# Display_Hour.net
KiCad netlist of a schematic drawn in Altium Designer
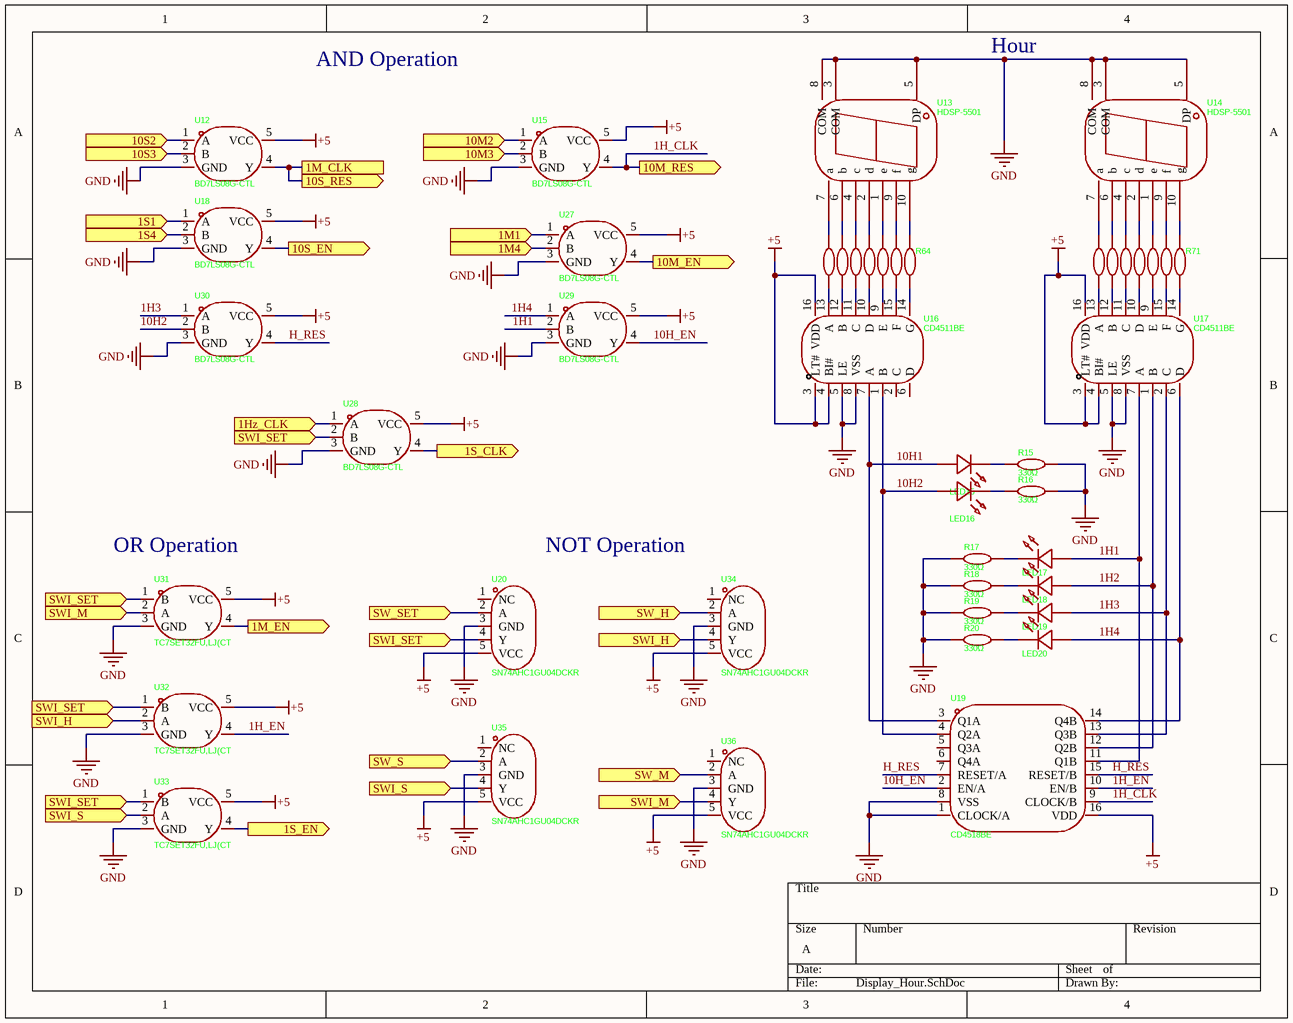
[diagram p0: Display_Hour.SchDoc]

(export (version "E")
  (design (tool "Eeschema 10.0.6"))
  (components
    (comp (ref "LED15")
      (value "WP7113ID")
      (footprint "LED-TH_BD5.0-P2.54-FD")
      (fields (field (name "MANUFACTURER") "Kingbright"))
      (libsource (lib "BCD_Clock_SCH_lib") (part "D_LED_2mm_red"))
    )
    (comp (ref "LED16")
      (value "WP7113ID")
      (footprint "LED-TH_BD5.0-P2.54-FD")
      (fields (field (name "MANUFACTURER") "Kingbright"))
      (libsource (lib "BCD_Clock_SCH_lib") (part "D_LED_2mm_red"))
    )
    (comp (ref "LED17")
      (value "WP7113ID")
      (footprint "LED-TH_BD5.0-P2.54-FD")
      (fields (field (name "MANUFACTURER") "Kingbright"))
      (libsource (lib "BCD_Clock_SCH_lib") (part "D_LED_2mm_red"))
    )
    (comp (ref "LED18")
      (value "WP7113ID")
      (footprint "LED-TH_BD5.0-P2.54-FD")
      (fields (field (name "MANUFACTURER") "Kingbright"))
      (libsource (lib "BCD_Clock_SCH_lib") (part "D_LED_2mm_red"))
    )
    (comp (ref "LED19")
      (value "WP7113ID")
      (footprint "LED-TH_BD5.0-P2.54-FD")
      (fields (field (name "MANUFACTURER") "Kingbright"))
      (libsource (lib "BCD_Clock_SCH_lib") (part "D_LED_2mm_red"))
    )
    (comp (ref "LED20")
      (value "WP7113ID")
      (footprint "LED-TH_BD5.0-P2.54-FD")
      (fields (field (name "MANUFACTURER") "Kingbright"))
      (libsource (lib "BCD_Clock_SCH_lib") (part "D_LED_2mm_red"))
    )
    (comp (ref "R15")
      (value "330Ω")
      (footprint "RES-TH_BD2.3-L6.5-P10.50-D0.5")
      (fields
        (field (name "MANUFACTURER") "CCO(千志电子)")
        (field (name "MANUFACTURER PART") "MF1/4W-330Ω±1% T")
        (field (name "TOLERANCE") "±1%")
      )
      (libsource (lib "BCD_Clock_SCH_lib") (part "Reg_330R_0.25W"))
    )
    (comp (ref "R16")
      (value "330Ω")
      (footprint "RES-TH_BD2.3-L6.5-P10.50-D0.5")
      (fields
        (field (name "MANUFACTURER") "CCO(千志电子)")
        (field (name "MANUFACTURER PART") "MF1/4W-330Ω±1% T")
        (field (name "TOLERANCE") "±1%")
      )
      (libsource (lib "BCD_Clock_SCH_lib") (part "Reg_330R_0.25W"))
    )
    (comp (ref "R17")
      (value "330Ω")
      (footprint "RES-TH_BD2.3-L6.5-P10.50-D0.5")
      (fields
        (field (name "MANUFACTURER") "CCO(千志电子)")
        (field (name "MANUFACTURER PART") "MF1/4W-330Ω±1% T")
        (field (name "TOLERANCE") "±1%")
      )
      (libsource (lib "BCD_Clock_SCH_lib") (part "Reg_330R_0.25W"))
    )
    (comp (ref "R18")
      (value "330Ω")
      (footprint "RES-TH_BD2.3-L6.5-P10.50-D0.5")
      (fields
        (field (name "MANUFACTURER") "CCO(千志电子)")
        (field (name "MANUFACTURER PART") "MF1/4W-330Ω±1% T")
        (field (name "TOLERANCE") "±1%")
      )
      (libsource (lib "BCD_Clock_SCH_lib") (part "Reg_330R_0.25W"))
    )
    (comp (ref "R19")
      (value "330Ω")
      (footprint "RES-TH_BD2.3-L6.5-P10.50-D0.5")
      (fields
        (field (name "MANUFACTURER") "CCO(千志电子)")
        (field (name "MANUFACTURER PART") "MF1/4W-330Ω±1% T")
        (field (name "TOLERANCE") "±1%")
      )
      (libsource (lib "BCD_Clock_SCH_lib") (part "Reg_330R_0.25W"))
    )
    (comp (ref "R20")
      (value "330Ω")
      (footprint "RES-TH_BD2.3-L6.5-P10.50-D0.5")
      (fields
        (field (name "MANUFACTURER") "CCO(千志电子)")
        (field (name "MANUFACTURER PART") "MF1/4W-330Ω±1% T")
        (field (name "TOLERANCE") "±1%")
      )
      (libsource (lib "BCD_Clock_SCH_lib") (part "Reg_330R_0.25W"))
    )
    (comp (ref "R58")
      (value "330Ω")
      (footprint "RES-TH_BD2.3-L6.5-P10.50-D0.5")
      (fields
        (field (name "MANUFACTURER") "CCO(千志电子)")
        (field (name "MANUFACTURER PART") "MF1/4W-330Ω±1% T")
        (field (name "TOLERANCE") "±1%")
      )
      (libsource (lib "BCD_Clock_SCH_lib") (part "Reg_330R_0.25W"))
    )
    (comp (ref "R59")
      (value "330Ω")
      (footprint "RES-TH_BD2.3-L6.5-P10.50-D0.5")
      (fields
        (field (name "MANUFACTURER") "CCO(千志电子)")
        (field (name "MANUFACTURER PART") "MF1/4W-330Ω±1% T")
        (field (name "TOLERANCE") "±1%")
      )
      (libsource (lib "BCD_Clock_SCH_lib") (part "Reg_330R_0.25W"))
    )
    (comp (ref "R60")
      (value "330Ω")
      (footprint "RES-TH_BD2.3-L6.5-P10.50-D0.5")
      (fields
        (field (name "MANUFACTURER") "CCO(千志电子)")
        (field (name "MANUFACTURER PART") "MF1/4W-330Ω±1% T")
        (field (name "TOLERANCE") "±1%")
      )
      (libsource (lib "BCD_Clock_SCH_lib") (part "Reg_330R_0.25W"))
    )
    (comp (ref "R61")
      (value "330Ω")
      (footprint "RES-TH_BD2.3-L6.5-P10.50-D0.5")
      (fields
        (field (name "MANUFACTURER") "CCO(千志电子)")
        (field (name "MANUFACTURER PART") "MF1/4W-330Ω±1% T")
        (field (name "TOLERANCE") "±1%")
      )
      (libsource (lib "BCD_Clock_SCH_lib") (part "Reg_330R_0.25W"))
    )
    (comp (ref "R62")
      (value "330Ω")
      (footprint "RES-TH_BD2.3-L6.5-P10.50-D0.5")
      (fields
        (field (name "MANUFACTURER") "CCO(千志电子)")
        (field (name "MANUFACTURER PART") "MF1/4W-330Ω±1% T")
        (field (name "TOLERANCE") "±1%")
      )
      (libsource (lib "BCD_Clock_SCH_lib") (part "Reg_330R_0.25W"))
    )
    (comp (ref "R63")
      (value "330Ω")
      (footprint "RES-TH_BD2.3-L6.5-P10.50-D0.5")
      (fields
        (field (name "MANUFACTURER") "CCO(千志电子)")
        (field (name "MANUFACTURER PART") "MF1/4W-330Ω±1% T")
        (field (name "TOLERANCE") "±1%")
      )
      (libsource (lib "BCD_Clock_SCH_lib") (part "Reg_330R_0.25W"))
    )
    (comp (ref "R64")
      (value "330Ω")
      (footprint "RES-TH_BD2.3-L6.5-P10.50-D0.5")
      (fields
        (field (name "MANUFACTURER") "CCO(千志电子)")
        (field (name "MANUFACTURER PART") "MF1/4W-330Ω±1% T")
        (field (name "TOLERANCE") "±1%")
      )
      (libsource (lib "BCD_Clock_SCH_lib") (part "Reg_330R_0.25W"))
    )
    (comp (ref "R65")
      (value "330Ω")
      (footprint "RES-TH_BD2.3-L6.5-P10.50-D0.5")
      (fields
        (field (name "MANUFACTURER") "CCO(千志电子)")
        (field (name "MANUFACTURER PART") "MF1/4W-330Ω±1% T")
        (field (name "TOLERANCE") "±1%")
      )
      (libsource (lib "BCD_Clock_SCH_lib") (part "Reg_330R_0.25W"))
    )
    (comp (ref "R66")
      (value "330Ω")
      (footprint "RES-TH_BD2.3-L6.5-P10.50-D0.5")
      (fields
        (field (name "MANUFACTURER") "CCO(千志电子)")
        (field (name "MANUFACTURER PART") "MF1/4W-330Ω±1% T")
        (field (name "TOLERANCE") "±1%")
      )
      (libsource (lib "BCD_Clock_SCH_lib") (part "Reg_330R_0.25W"))
    )
    (comp (ref "R67")
      (value "330Ω")
      (footprint "RES-TH_BD2.3-L6.5-P10.50-D0.5")
      (fields
        (field (name "MANUFACTURER") "CCO(千志电子)")
        (field (name "MANUFACTURER PART") "MF1/4W-330Ω±1% T")
        (field (name "TOLERANCE") "±1%")
      )
      (libsource (lib "BCD_Clock_SCH_lib") (part "Reg_330R_0.25W"))
    )
    (comp (ref "R68")
      (value "330Ω")
      (footprint "RES-TH_BD2.3-L6.5-P10.50-D0.5")
      (fields
        (field (name "MANUFACTURER") "CCO(千志电子)")
        (field (name "MANUFACTURER PART") "MF1/4W-330Ω±1% T")
        (field (name "TOLERANCE") "±1%")
      )
      (libsource (lib "BCD_Clock_SCH_lib") (part "Reg_330R_0.25W"))
    )
    (comp (ref "R69")
      (value "330Ω")
      (footprint "RES-TH_BD2.3-L6.5-P10.50-D0.5")
      (fields
        (field (name "MANUFACTURER") "CCO(千志电子)")
        (field (name "MANUFACTURER PART") "MF1/4W-330Ω±1% T")
        (field (name "TOLERANCE") "±1%")
      )
      (libsource (lib "BCD_Clock_SCH_lib") (part "Reg_330R_0.25W"))
    )
    (comp (ref "R70")
      (value "330Ω")
      (footprint "RES-TH_BD2.3-L6.5-P10.50-D0.5")
      (fields
        (field (name "MANUFACTURER") "CCO(千志电子)")
        (field (name "MANUFACTURER PART") "MF1/4W-330Ω±1% T")
        (field (name "TOLERANCE") "±1%")
      )
      (libsource (lib "BCD_Clock_SCH_lib") (part "Reg_330R_0.25W"))
    )
    (comp (ref "R71")
      (value "330Ω")
      (footprint "RES-TH_BD2.3-L6.5-P10.50-D0.5")
      (fields
        (field (name "MANUFACTURER") "CCO(千志电子)")
        (field (name "MANUFACTURER PART") "MF1/4W-330Ω±1% T")
        (field (name "TOLERANCE") "±1%")
      )
      (libsource (lib "BCD_Clock_SCH_lib") (part "Reg_330R_0.25W"))
    )
    (comp (ref "U12")
      (value "BD7LS08G-CTL")
      (footprint "SSOP-5_L3.0-W1.6-P0.95-LS2.8-BR")
      (fields (field (name "MANUFACTURER") "ROHM(罗姆)"))
      (libsource (lib "BCD_Clock_SCH_lib") (part "AND_BD7LS08G-CTL"))
    )
    (comp (ref "U13")
      (value "HDSP-5501")
      (footprint "LED-SEG-TH_HDSP-A")
      (fields (field (name "MANUFACTURER") "Broadcom/AVAGO(安华高)"))
      (libsource (lib "BCD_Clock_SCH_lib") (part "HDSP-5501"))
    )
    (comp (ref "U14")
      (value "HDSP-5501")
      (footprint "LED-SEG-TH_HDSP-A")
      (fields (field (name "MANUFACTURER") "Broadcom/AVAGO(安华高)"))
      (libsource (lib "BCD_Clock_SCH_lib") (part "HDSP-5501"))
    )
    (comp (ref "U15")
      (value "BD7LS08G-CTL")
      (footprint "SSOP-5_L3.0-W1.6-P0.95-LS2.8-BR")
      (fields (field (name "MANUFACTURER") "ROHM(罗姆)"))
      (libsource (lib "BCD_Clock_SCH_lib") (part "AND_BD7LS08G-CTL"))
    )
    (comp (ref "U16")
      (value "CD4511BE")
      (footprint "DIP-16_L19.8-W6.5-P2.54-LS7.6-BL")
      (fields (field (name "MANUFACTURER") "HGSEMI(华冠)"))
      (libsource (lib "BCD_Clock_SCH_lib") (part "CD4511BE_C507153"))
    )
    (comp (ref "U17")
      (value "CD4511BE")
      (footprint "DIP-16_L19.8-W6.5-P2.54-LS7.6-BL")
      (fields (field (name "MANUFACTURER") "HGSEMI(华冠)"))
      (libsource (lib "BCD_Clock_SCH_lib") (part "CD4511BE_C507153"))
    )
    (comp (ref "U18")
      (value "BD7LS08G-CTL")
      (footprint "SSOP-5_L3.0-W1.6-P0.95-LS2.8-BR")
      (fields (field (name "MANUFACTURER") "ROHM(罗姆)"))
      (libsource (lib "BCD_Clock_SCH_lib") (part "AND_BD7LS08G-CTL"))
    )
    (comp (ref "U19")
      (value "CD4518BE")
      (footprint "DIP-16_L19.3-W6.4-P2.54-LS7.6-BL")
      (fields (field (name "MANUFACTURER") "TI(德州仪器)"))
      (libsource (lib "BCD_Clock_SCH_lib") (part "CD4518BE"))
    )
    (comp (ref "U20")
      (value "SN74AHC1GU04DCKR")
      (footprint "SOT-353_L2.1-W1.3-P0.65-LS2.3-BR")
      (fields (field (name "MANUFACTURER") "TI(德州仪器)"))
      (libsource (lib "BCD_Clock_SCH_lib") (part "NOT_SN74AHC1GU04DCKR_C7472"))
    )
    (comp (ref "U27")
      (value "BD7LS08G-CTL")
      (footprint "SSOP-5_L3.0-W1.6-P0.95-LS2.8-BR")
      (fields (field (name "MANUFACTURER") "ROHM(罗姆)"))
      (libsource (lib "BCD_Clock_SCH_lib") (part "AND_BD7LS08G-CTL"))
    )
    (comp (ref "U28")
      (value "BD7LS08G-CTL")
      (footprint "SSOP-5_L3.0-W1.6-P0.95-LS2.8-BR")
      (fields (field (name "MANUFACTURER") "ROHM(罗姆)"))
      (libsource (lib "BCD_Clock_SCH_lib") (part "AND_BD7LS08G-CTL"))
    )
    (comp (ref "U29")
      (value "BD7LS08G-CTL")
      (footprint "SSOP-5_L3.0-W1.6-P0.95-LS2.8-BR")
      (fields (field (name "MANUFACTURER") "ROHM(罗姆)"))
      (libsource (lib "BCD_Clock_SCH_lib") (part "AND_BD7LS08G-CTL"))
    )
    (comp (ref "U30")
      (value "BD7LS08G-CTL")
      (footprint "SSOP-5_L3.0-W1.6-P0.95-LS2.8-BR")
      (fields (field (name "MANUFACTURER") "ROHM(罗姆)"))
      (libsource (lib "BCD_Clock_SCH_lib") (part "AND_BD7LS08G-CTL"))
    )
    (comp (ref "U31")
      (value "TC7SET32FU,LJ(CT")
      (footprint "TSSOP-5_L2.0-W1.3-P0.65-LS2.1-BR")
      (fields (field (name "MANUFACTURER") "TOSHIBA(东芝)"))
      (libsource (lib "BCD_Clock_SCH_lib") (part "OR_GATE_TC7SET32FU,LJ(CT"))
    )
    (comp (ref "U32")
      (value "TC7SET32FU,LJ(CT")
      (footprint "TSSOP-5_L2.0-W1.3-P0.65-LS2.1-BR")
      (fields (field (name "MANUFACTURER") "TOSHIBA(东芝)"))
      (libsource (lib "BCD_Clock_SCH_lib") (part "OR_GATE_TC7SET32FU,LJ(CT"))
    )
    (comp (ref "U33")
      (value "TC7SET32FU,LJ(CT")
      (footprint "TSSOP-5_L2.0-W1.3-P0.65-LS2.1-BR")
      (fields (field (name "MANUFACTURER") "TOSHIBA(东芝)"))
      (libsource (lib "BCD_Clock_SCH_lib") (part "OR_GATE_TC7SET32FU,LJ(CT"))
    )
    (comp (ref "U34")
      (value "SN74AHC1GU04DCKR")
      (footprint "SOT-353_L2.1-W1.3-P0.65-LS2.3-BR")
      (fields (field (name "MANUFACTURER") "TI(德州仪器)"))
      (libsource (lib "BCD_Clock_SCH_lib") (part "NOT_SN74AHC1GU04DCKR_C7472"))
    )
    (comp (ref "U35")
      (value "SN74AHC1GU04DCKR")
      (footprint "SOT-353_L2.1-W1.3-P0.65-LS2.3-BR")
      (fields (field (name "MANUFACTURER") "TI(德州仪器)"))
      (libsource (lib "BCD_Clock_SCH_lib") (part "NOT_SN74AHC1GU04DCKR_C7472"))
    )
    (comp (ref "U36")
      (value "SN74AHC1GU04DCKR")
      (footprint "SOT-353_L2.1-W1.3-P0.65-LS2.3-BR")
      (fields (field (name "MANUFACTURER") "TI(德州仪器)"))
      (libsource (lib "BCD_Clock_SCH_lib") (part "NOT_SN74AHC1GU04DCKR_C7472"))
    )
  )
  (nets
    (net (code "1") (name "+5") (class "Default")
      (node (ref "U12") (pin "5") (pinfunction "VCC_5") (pintype "passive"))
      (node (ref "U15") (pin "5") (pinfunction "VCC_5") (pintype "passive"))
      (node (ref "U16") (pin "16") (pinfunction "VDD_16") (pintype "passive"))
      (node (ref "U16") (pin "3") (pinfunction "LT#_3") (pintype "passive"))
      (node (ref "U16") (pin "4") (pinfunction "BI#_4") (pintype "passive"))
      (node (ref "U17") (pin "16") (pinfunction "VDD_16") (pintype "passive"))
      (node (ref "U17") (pin "3") (pinfunction "LT#_3") (pintype "passive"))
      (node (ref "U17") (pin "4") (pinfunction "BI#_4") (pintype "passive"))
      (node (ref "U18") (pin "5") (pinfunction "VCC_5") (pintype "passive"))
      (node (ref "U19") (pin "16") (pinfunction "VDD_16") (pintype "passive"))
      (node (ref "U20") (pin "5") (pinfunction "VCC_5") (pintype "passive"))
      (node (ref "U27") (pin "5") (pinfunction "VCC_5") (pintype "passive"))
      (node (ref "U28") (pin "5") (pinfunction "VCC_5") (pintype "passive"))
      (node (ref "U29") (pin "5") (pinfunction "VCC_5") (pintype "passive"))
      (node (ref "U30") (pin "5") (pinfunction "VCC_5") (pintype "passive"))
      (node (ref "U31") (pin "5") (pinfunction "VCC_5") (pintype "passive"))
      (node (ref "U32") (pin "5") (pinfunction "VCC_5") (pintype "passive"))
      (node (ref "U33") (pin "5") (pinfunction "VCC_5") (pintype "passive"))
      (node (ref "U34") (pin "5") (pinfunction "VCC_5") (pintype "passive"))
      (node (ref "U35") (pin "5") (pinfunction "VCC_5") (pintype "passive"))
      (node (ref "U36") (pin "5") (pinfunction "VCC_5") (pintype "passive"))
    )
    (net (code "2") (name "/1H1") (class "Default")
      (node (ref "LED17") (pin "1") (pinfunction "A_1") (pintype "passive"))
      (node (ref "U17") (pin "7") (pinfunction "A_7") (pintype "passive"))
      (node (ref "U19") (pin "11") (pinfunction "Q1B_11") (pintype "passive"))
      (node (ref "U29") (pin "2") (pinfunction "B_2") (pintype "passive"))
    )
    (net (code "3") (name "/1H2") (class "Default")
      (node (ref "LED18") (pin "1") (pinfunction "A_1") (pintype "passive"))
      (node (ref "U17") (pin "1") (pinfunction "B_1") (pintype "passive"))
      (node (ref "U19") (pin "12") (pinfunction "Q2B_12") (pintype "passive"))
    )
    (net (code "4") (name "/1H3") (class "Default")
      (node (ref "LED19") (pin "1") (pinfunction "A_1") (pintype "passive"))
      (node (ref "U17") (pin "2") (pinfunction "C_2") (pintype "passive"))
      (node (ref "U19") (pin "13") (pinfunction "Q3B_13") (pintype "passive"))
      (node (ref "U30") (pin "1") (pinfunction "A_1") (pintype "passive"))
    )
    (net (code "5") (name "/1H4") (class "Default")
      (node (ref "LED20") (pin "1") (pinfunction "A_1") (pintype "passive"))
      (node (ref "U17") (pin "6") (pinfunction "D_6") (pintype "passive"))
      (node (ref "U19") (pin "14") (pinfunction "Q4B_14") (pintype "passive"))
      (node (ref "U29") (pin "1") (pinfunction "A_1") (pintype "passive"))
    )
    (net (code "6") (name "/1H_CLK") (class "Default")
      (node (ref "U15") (pin "4") (pinfunction "Y_4") (pintype "passive"))
      (node (ref "U19") (pin "9") (pinfunction "CLOCK/B_9") (pintype "passive"))
    )
    (net (code "7") (name "/1H_EN") (class "Default")
      (node (ref "U19") (pin "10") (pinfunction "EN/B_10") (pintype "passive"))
      (node (ref "U32") (pin "4") (pinfunction "Y_4") (pintype "passive"))
    )
    (net (code "8") (name "/1Hz_CLK") (class "Default")
      (node (ref "U28") (pin "1") (pinfunction "A_1") (pintype "passive"))
    )
    (net (code "9") (name "/1M1") (class "Default")
      (node (ref "U27") (pin "1") (pinfunction "A_1") (pintype "passive"))
    )
    (net (code "10") (name "/1M4") (class "Default")
      (node (ref "U27") (pin "2") (pinfunction "B_2") (pintype "passive"))
    )
    (net (code "11") (name "/1M_EN") (class "Default")
      (node (ref "U31") (pin "4") (pinfunction "Y_4") (pintype "passive"))
    )
    (net (code "12") (name "/1S1") (class "Default")
      (node (ref "U18") (pin "1") (pinfunction "A_1") (pintype "passive"))
    )
    (net (code "13") (name "/1S4") (class "Default")
      (node (ref "U18") (pin "2") (pinfunction "B_2") (pintype "passive"))
    )
    (net (code "14") (name "/1S_CLK") (class "Default")
      (node (ref "U28") (pin "4") (pinfunction "Y_4") (pintype "passive"))
    )
    (net (code "15") (name "/1S_EN") (class "Default")
      (node (ref "U33") (pin "4") (pinfunction "Y_4") (pintype "passive"))
    )
    (net (code "16") (name "/10H1") (class "Default")
      (node (ref "LED15") (pin "1") (pinfunction "A_1") (pintype "passive"))
      (node (ref "U16") (pin "7") (pinfunction "A_7") (pintype "passive"))
      (node (ref "U19") (pin "3") (pinfunction "Q1A_3") (pintype "passive"))
    )
    (net (code "17") (name "/10H2") (class "Default")
      (node (ref "LED16") (pin "1") (pinfunction "A_1") (pintype "passive"))
      (node (ref "U16") (pin "1") (pinfunction "B_1") (pintype "passive"))
      (node (ref "U19") (pin "4") (pinfunction "Q2A_4") (pintype "passive"))
      (node (ref "U30") (pin "2") (pinfunction "B_2") (pintype "passive"))
    )
    (net (code "18") (name "/10H_EN") (class "Default")
      (node (ref "U19") (pin "2") (pinfunction "EN/A_2") (pintype "passive"))
      (node (ref "U29") (pin "4") (pinfunction "Y_4") (pintype "passive"))
    )
    (net (code "19") (name "/10M2") (class "Default")
      (node (ref "U15") (pin "1") (pinfunction "A_1") (pintype "passive"))
    )
    (net (code "20") (name "/10M3") (class "Default")
      (node (ref "U15") (pin "2") (pinfunction "B_2") (pintype "passive"))
    )
    (net (code "21") (name "/10M_EN") (class "Default")
      (node (ref "U27") (pin "4") (pinfunction "Y_4") (pintype "passive"))
    )
    (net (code "22") (name "/10S2") (class "Default")
      (node (ref "U12") (pin "1") (pinfunction "A_1") (pintype "passive"))
    )
    (net (code "23") (name "/10S3") (class "Default")
      (node (ref "U12") (pin "2") (pinfunction "B_2") (pintype "passive"))
    )
    (net (code "24") (name "/10S_EN") (class "Default")
      (node (ref "U18") (pin "4") (pinfunction "Y_4") (pintype "passive"))
    )
    (net (code "25") (name "/10S_RES") (class "Default")
      (node (ref "U12") (pin "4") (pinfunction "Y_4") (pintype "passive"))
    )
    (net (code "26") (name "/H_RES") (class "Default")
      (node (ref "U19") (pin "15") (pinfunction "RESET/B_15") (pintype "passive"))
      (node (ref "U19") (pin "7") (pinfunction "RESET/A_7") (pintype "passive"))
      (node (ref "U30") (pin "4") (pinfunction "Y_4") (pintype "passive"))
    )
    (net (code "27") (name "/SWI_H") (class "Default")
      (node (ref "U32") (pin "2") (pinfunction "A_2") (pintype "passive"))
      (node (ref "U34") (pin "4") (pinfunction "Y_4") (pintype "passive"))
    )
    (net (code "28") (name "/SWI_M") (class "Default")
      (node (ref "U31") (pin "2") (pinfunction "A_2") (pintype "passive"))
      (node (ref "U36") (pin "4") (pinfunction "Y_4") (pintype "passive"))
    )
    (net (code "29") (name "/SWI_S") (class "Default")
      (node (ref "U33") (pin "2") (pinfunction "A_2") (pintype "passive"))
      (node (ref "U35") (pin "4") (pinfunction "Y_4") (pintype "passive"))
    )
    (net (code "30") (name "/SWI_SET") (class "Default")
      (node (ref "U20") (pin "4") (pinfunction "Y_4") (pintype "passive"))
      (node (ref "U28") (pin "2") (pinfunction "B_2") (pintype "passive"))
      (node (ref "U31") (pin "1") (pinfunction "B_1") (pintype "passive"))
      (node (ref "U32") (pin "1") (pinfunction "B_1") (pintype "passive"))
      (node (ref "U33") (pin "1") (pinfunction "B_1") (pintype "passive"))
    )
    (net (code "31") (name "/SW_H") (class "Default")
      (node (ref "U34") (pin "2") (pinfunction "A_2") (pintype "passive"))
    )
    (net (code "32") (name "/SW_M") (class "Default")
      (node (ref "U36") (pin "2") (pinfunction "A_2") (pintype "passive"))
    )
    (net (code "33") (name "/SW_S") (class "Default")
      (node (ref "U35") (pin "2") (pinfunction "A_2") (pintype "passive"))
    )
    (net (code "34") (name "/SW_SET") (class "Default")
      (node (ref "U20") (pin "2") (pinfunction "A_2") (pintype "passive"))
    )
    (net (code "35") (name "GND") (class "Default")
      (node (ref "R15") (pin "2") (pinfunction "2_2") (pintype "passive"))
      (node (ref "R16") (pin "2") (pinfunction "2_2") (pintype "passive"))
      (node (ref "R17") (pin "1") (pinfunction "1_1") (pintype "passive"))
      (node (ref "R18") (pin "1") (pinfunction "1_1") (pintype "passive"))
      (node (ref "R19") (pin "1") (pinfunction "1_1") (pintype "passive"))
      (node (ref "R20") (pin "1") (pinfunction "1_1") (pintype "passive"))
      (node (ref "U12") (pin "3") (pinfunction "GND_3") (pintype "passive"))
      (node (ref "U13") (pin "3") (pinfunction "COM_3") (pintype "passive"))
      (node (ref "U13") (pin "5") (pinfunction "DP_5") (pintype "passive"))
      (node (ref "U13") (pin "8") (pinfunction "COM_8") (pintype "passive"))
      (node (ref "U14") (pin "3") (pinfunction "COM_3") (pintype "passive"))
      (node (ref "U14") (pin "5") (pinfunction "DP_5") (pintype "passive"))
      (node (ref "U14") (pin "8") (pinfunction "COM_8") (pintype "passive"))
      (node (ref "U15") (pin "3") (pinfunction "GND_3") (pintype "passive"))
      (node (ref "U16") (pin "5") (pinfunction "LE_5") (pintype "passive"))
      (node (ref "U16") (pin "8") (pinfunction "VSS_8") (pintype "passive"))
      (node (ref "U17") (pin "5") (pinfunction "LE_5") (pintype "passive"))
      (node (ref "U17") (pin "8") (pinfunction "VSS_8") (pintype "passive"))
      (node (ref "U18") (pin "3") (pinfunction "GND_3") (pintype "passive"))
      (node (ref "U19") (pin "1") (pinfunction "CLOCK/A_1") (pintype "passive"))
      (node (ref "U19") (pin "8") (pinfunction "VSS_8") (pintype "passive"))
      (node (ref "U20") (pin "3") (pinfunction "GND_3") (pintype "passive"))
      (node (ref "U27") (pin "3") (pinfunction "GND_3") (pintype "passive"))
      (node (ref "U28") (pin "3") (pinfunction "GND_3") (pintype "passive"))
      (node (ref "U29") (pin "3") (pinfunction "GND_3") (pintype "passive"))
      (node (ref "U30") (pin "3") (pinfunction "GND_3") (pintype "passive"))
      (node (ref "U31") (pin "3") (pinfunction "GND_3") (pintype "passive"))
      (node (ref "U32") (pin "3") (pinfunction "GND_3") (pintype "passive"))
      (node (ref "U33") (pin "3") (pinfunction "GND_3") (pintype "passive"))
      (node (ref "U34") (pin "3") (pinfunction "GND_3") (pintype "passive"))
      (node (ref "U35") (pin "3") (pinfunction "GND_3") (pintype "passive"))
      (node (ref "U36") (pin "3") (pinfunction "GND_3") (pintype "passive"))
    )
    (net (code "36") (name "Net-(LED15-K)") (class "Default")
      (node (ref "LED15") (pin "2") (pinfunction "K_2") (pintype "passive"))
      (node (ref "R15") (pin "1") (pinfunction "1_1") (pintype "passive"))
    )
    (net (code "37") (name "Net-(LED16-K)") (class "Default")
      (node (ref "LED16") (pin "2") (pinfunction "K_2") (pintype "passive"))
      (node (ref "R16") (pin "1") (pinfunction "1_1") (pintype "passive"))
    )
    (net (code "38") (name "Net-(LED17-K)") (class "Default")
      (node (ref "LED17") (pin "2") (pinfunction "K_2") (pintype "passive"))
      (node (ref "R17") (pin "2") (pinfunction "2_2") (pintype "passive"))
    )
    (net (code "39") (name "Net-(LED18-K)") (class "Default")
      (node (ref "LED18") (pin "2") (pinfunction "K_2") (pintype "passive"))
      (node (ref "R18") (pin "2") (pinfunction "2_2") (pintype "passive"))
    )
    (net (code "40") (name "Net-(LED19-K)") (class "Default")
      (node (ref "LED19") (pin "2") (pinfunction "K_2") (pintype "passive"))
      (node (ref "R19") (pin "2") (pinfunction "2_2") (pintype "passive"))
    )
    (net (code "41") (name "Net-(LED20-K)") (class "Default")
      (node (ref "LED20") (pin "2") (pinfunction "K_2") (pintype "passive"))
      (node (ref "R20") (pin "2") (pinfunction "2_2") (pintype "passive"))
    )
    (net (code "42") (name "Net-(R58-Pad1)") (class "Default")
      (node (ref "R58") (pin "1") (pinfunction "1_1") (pintype "passive"))
      (node (ref "U16") (pin "13") (pinfunction "A_13") (pintype "passive"))
    )
    (net (code "43") (name "Net-(R59-Pad1)") (class "Default")
      (node (ref "R59") (pin "1") (pinfunction "1_1") (pintype "passive"))
      (node (ref "U16") (pin "12") (pinfunction "B_12") (pintype "passive"))
    )
    (net (code "44") (name "Net-(R60-Pad1)") (class "Default")
      (node (ref "R60") (pin "1") (pinfunction "1_1") (pintype "passive"))
      (node (ref "U16") (pin "11") (pinfunction "C_11") (pintype "passive"))
    )
    (net (code "45") (name "Net-(R61-Pad1)") (class "Default")
      (node (ref "R61") (pin "1") (pinfunction "1_1") (pintype "passive"))
      (node (ref "U16") (pin "10") (pinfunction "D_10") (pintype "passive"))
    )
    (net (code "46") (name "Net-(R65-Pad1)") (class "Default")
      (node (ref "R65") (pin "1") (pinfunction "1_1") (pintype "passive"))
      (node (ref "U17") (pin "13") (pinfunction "A_13") (pintype "passive"))
    )
    (net (code "47") (name "Net-(R66-Pad1)") (class "Default")
      (node (ref "R66") (pin "1") (pinfunction "1_1") (pintype "passive"))
      (node (ref "U17") (pin "12") (pinfunction "B_12") (pintype "passive"))
    )
    (net (code "48") (name "Net-(R67-Pad1)") (class "Default")
      (node (ref "R67") (pin "1") (pinfunction "1_1") (pintype "passive"))
      (node (ref "U17") (pin "11") (pinfunction "C_11") (pintype "passive"))
    )
    (net (code "49") (name "Net-(R68-Pad1)") (class "Default")
      (node (ref "R68") (pin "1") (pinfunction "1_1") (pintype "passive"))
      (node (ref "U17") (pin "10") (pinfunction "D_10") (pintype "passive"))
    )
    (net (code "50") (name "Net-(U13-a)") (class "Default")
      (node (ref "R58") (pin "2") (pinfunction "2_2") (pintype "passive"))
      (node (ref "U13") (pin "7") (pinfunction "a_7") (pintype "passive"))
    )
    (net (code "51") (name "Net-(U13-b)") (class "Default")
      (node (ref "R59") (pin "2") (pinfunction "2_2") (pintype "passive"))
      (node (ref "U13") (pin "6") (pinfunction "b_6") (pintype "passive"))
    )
    (net (code "52") (name "Net-(U13-c)") (class "Default")
      (node (ref "R60") (pin "2") (pinfunction "2_2") (pintype "passive"))
      (node (ref "U13") (pin "4") (pinfunction "c_4") (pintype "passive"))
    )
    (net (code "53") (name "Net-(U13-d)") (class "Default")
      (node (ref "R61") (pin "2") (pinfunction "2_2") (pintype "passive"))
      (node (ref "U13") (pin "2") (pinfunction "d_2") (pintype "passive"))
    )
    (net (code "54") (name "Net-(U13-e)") (class "Default")
      (node (ref "R62") (pin "2") (pinfunction "2_2") (pintype "passive"))
      (node (ref "U13") (pin "1") (pinfunction "e_1") (pintype "passive"))
    )
    (net (code "55") (name "Net-(U13-f)") (class "Default")
      (node (ref "R63") (pin "2") (pinfunction "2_2") (pintype "passive"))
      (node (ref "U13") (pin "9") (pinfunction "f_9") (pintype "passive"))
    )
    (net (code "56") (name "Net-(U13-g)") (class "Default")
      (node (ref "R64") (pin "2") (pinfunction "2_2") (pintype "passive"))
      (node (ref "U13") (pin "10") (pinfunction "g_10") (pintype "passive"))
    )
    (net (code "57") (name "Net-(U14-a)") (class "Default")
      (node (ref "R65") (pin "2") (pinfunction "2_2") (pintype "passive"))
      (node (ref "U14") (pin "7") (pinfunction "a_7") (pintype "passive"))
    )
    (net (code "58") (name "Net-(U14-b)") (class "Default")
      (node (ref "R66") (pin "2") (pinfunction "2_2") (pintype "passive"))
      (node (ref "U14") (pin "6") (pinfunction "b_6") (pintype "passive"))
    )
    (net (code "59") (name "Net-(U14-c)") (class "Default")
      (node (ref "R67") (pin "2") (pinfunction "2_2") (pintype "passive"))
      (node (ref "U14") (pin "4") (pinfunction "c_4") (pintype "passive"))
    )
    (net (code "60") (name "Net-(U14-d)") (class "Default")
      (node (ref "R68") (pin "2") (pinfunction "2_2") (pintype "passive"))
      (node (ref "U14") (pin "2") (pinfunction "d_2") (pintype "passive"))
    )
    (net (code "61") (name "Net-(U14-e)") (class "Default")
      (node (ref "R69") (pin "2") (pinfunction "2_2") (pintype "passive"))
      (node (ref "U14") (pin "1") (pinfunction "e_1") (pintype "passive"))
    )
    (net (code "62") (name "Net-(U14-f)") (class "Default")
      (node (ref "R70") (pin "2") (pinfunction "2_2") (pintype "passive"))
      (node (ref "U14") (pin "9") (pinfunction "f_9") (pintype "passive"))
    )
    (net (code "63") (name "Net-(U14-g)") (class "Default")
      (node (ref "R71") (pin "2") (pinfunction "2_2") (pintype "passive"))
      (node (ref "U14") (pin "10") (pinfunction "g_10") (pintype "passive"))
    )
    (net (code "64") (name "Net-(U16-E)") (class "Default")
      (node (ref "R62") (pin "1") (pinfunction "1_1") (pintype "passive"))
      (node (ref "U16") (pin "9") (pinfunction "E_9") (pintype "passive"))
    )
    (net (code "65") (name "Net-(U16-F)") (class "Default")
      (node (ref "R63") (pin "1") (pinfunction "1_1") (pintype "passive"))
      (node (ref "U16") (pin "15") (pinfunction "F_15") (pintype "passive"))
    )
    (net (code "66") (name "Net-(U16-G)") (class "Default")
      (node (ref "R64") (pin "1") (pinfunction "1_1") (pintype "passive"))
      (node (ref "U16") (pin "14") (pinfunction "G_14") (pintype "passive"))
    )
    (net (code "67") (name "Net-(U17-E)") (class "Default")
      (node (ref "R69") (pin "1") (pinfunction "1_1") (pintype "passive"))
      (node (ref "U17") (pin "9") (pinfunction "E_9") (pintype "passive"))
    )
    (net (code "68") (name "Net-(U17-F)") (class "Default")
      (node (ref "R70") (pin "1") (pinfunction "1_1") (pintype "passive"))
      (node (ref "U17") (pin "15") (pinfunction "F_15") (pintype "passive"))
    )
    (net (code "69") (name "Net-(U17-G)") (class "Default")
      (node (ref "R71") (pin "1") (pinfunction "1_1") (pintype "passive"))
      (node (ref "U17") (pin "14") (pinfunction "G_14") (pintype "passive"))
    )
    (net (code "70") (name "unconnected-(U16-C-Pad2)") (class "Default")
      (node (ref "U16") (pin "2") (pinfunction "C_2") (pintype "passive"))
    )
    (net (code "71") (name "unconnected-(U16-D-Pad6)") (class "Default")
      (node (ref "U16") (pin "6") (pinfunction "D_6") (pintype "passive"))
    )
    (net (code "72") (name "unconnected-(U19-Q3A-Pad5)") (class "Default")
      (node (ref "U19") (pin "5") (pinfunction "Q3A_5") (pintype "passive"))
    )
    (net (code "73") (name "unconnected-(U19-Q4A-Pad6)") (class "Default")
      (node (ref "U19") (pin "6") (pinfunction "Q4A_6") (pintype "passive"))
    )
    (net (code "74") (name "unconnected-(U20-NC-Pad1)") (class "Default")
      (node (ref "U20") (pin "1") (pinfunction "NC_1") (pintype "passive"))
    )
    (net (code "75") (name "unconnected-(U34-NC-Pad1)") (class "Default")
      (node (ref "U34") (pin "1") (pinfunction "NC_1") (pintype "passive"))
    )
    (net (code "76") (name "unconnected-(U35-NC-Pad1)") (class "Default")
      (node (ref "U35") (pin "1") (pinfunction "NC_1") (pintype "passive"))
    )
    (net (code "77") (name "unconnected-(U36-NC-Pad1)") (class "Default")
      (node (ref "U36") (pin "1") (pinfunction "NC_1") (pintype "passive"))
    )
  )
)
